# It-s_Time_Do.net
KiCad netlist of a schematic drawn in EAGLE
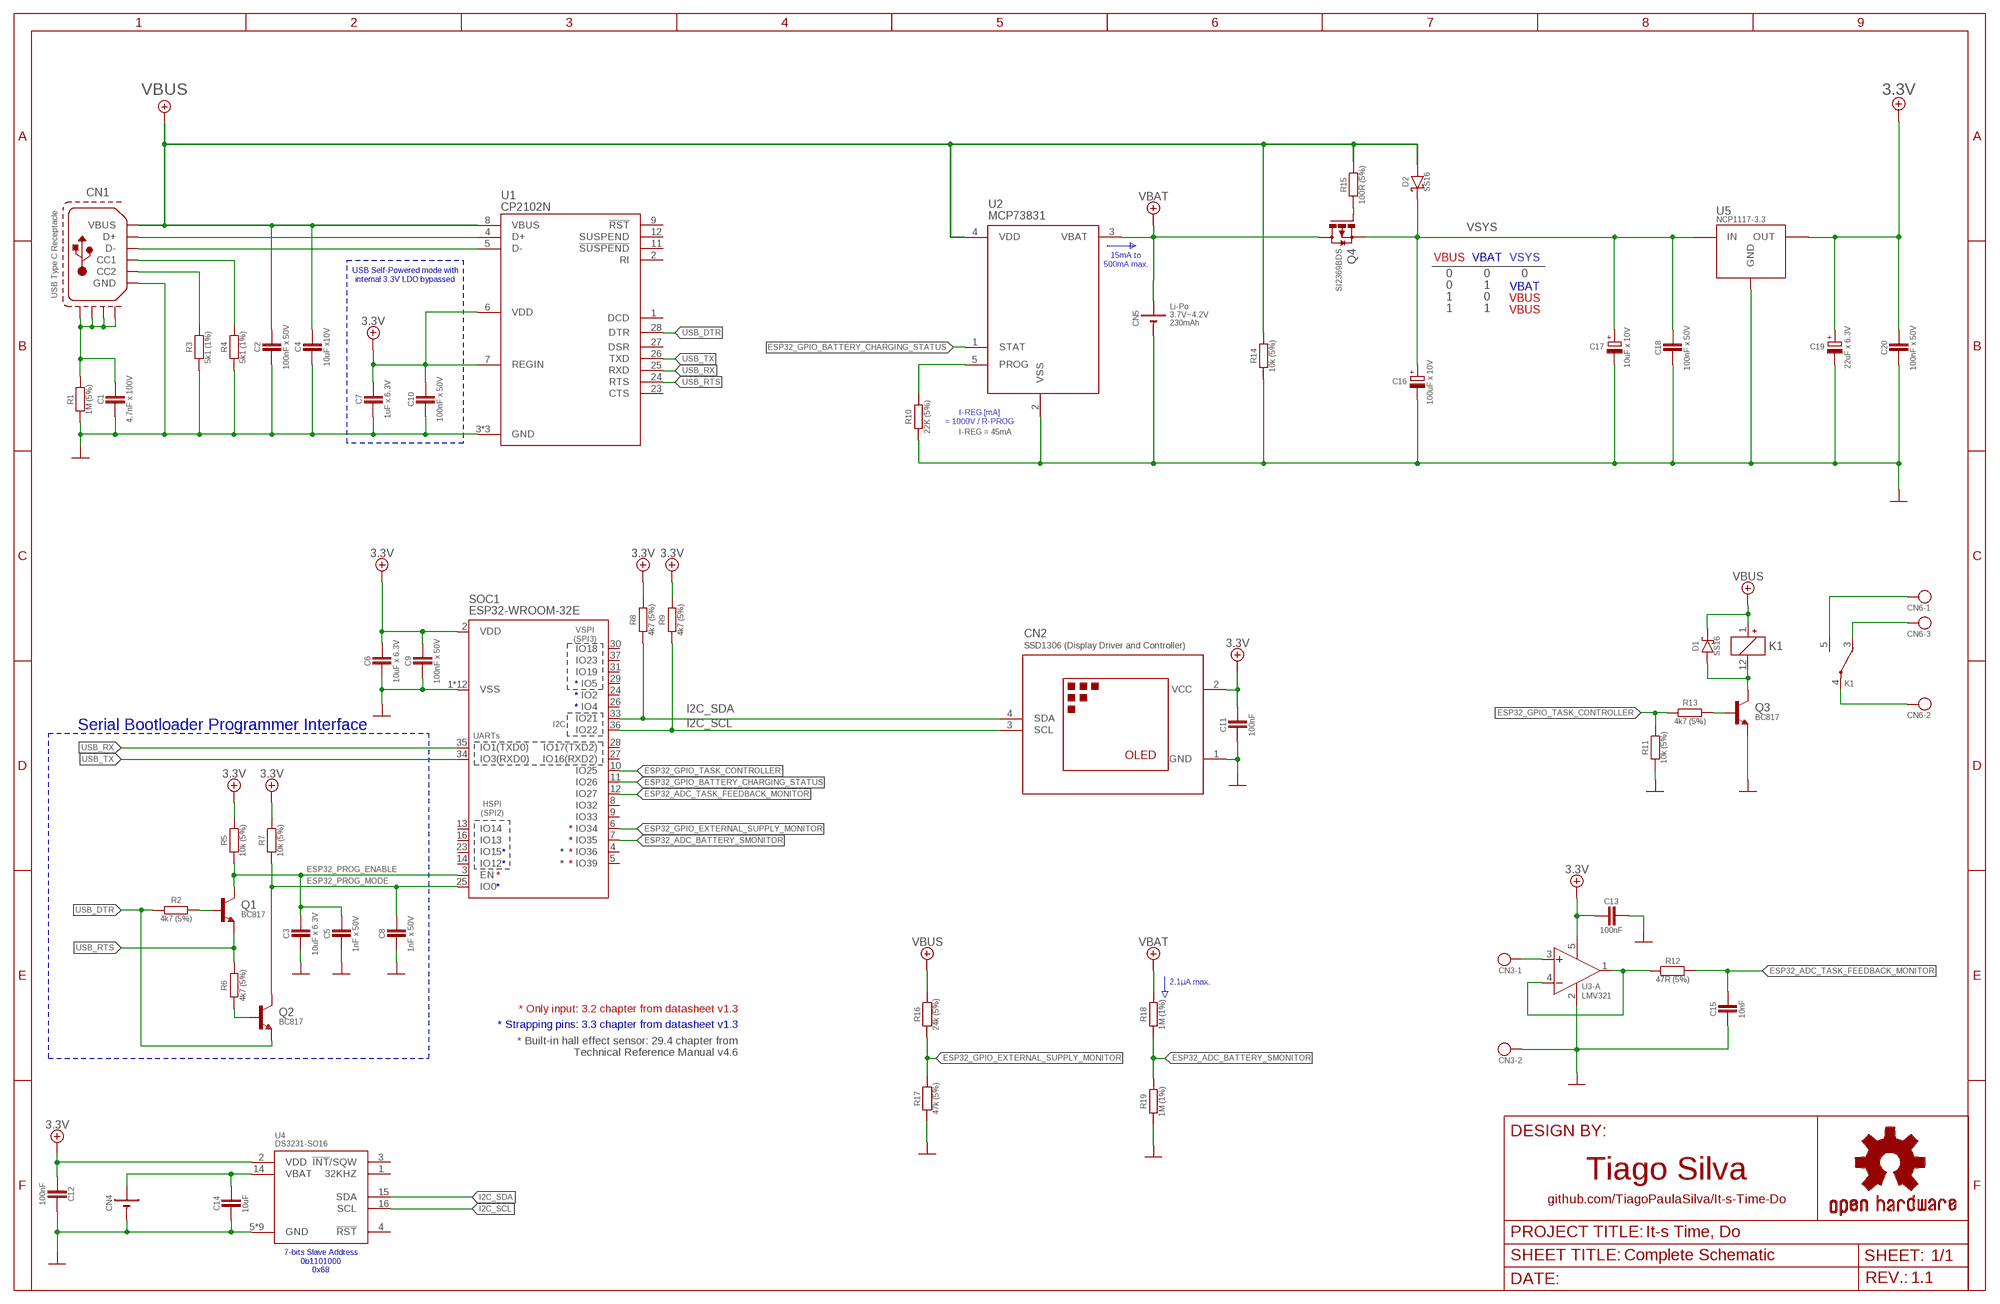
[diagram p0: schematic, sheet 1]

(export (version "E")
  (design (tool "Eeschema 10.0.6"))
  (components
    (comp (ref "C1")
      (value "4.7nF x 100V")
      (footprint "eagle-import:C0603")
      (libsource (lib "eagle-import") (part "C_0603"))
    )
    (comp (ref "C2")
      (value "100nF x 50V")
      (footprint "eagle-import:C0603")
      (libsource (lib "eagle-import") (part "C_0603"))
    )
    (comp (ref "C3")
      (value "10uF x 6.3V")
      (footprint "eagle-import:C0603")
      (libsource (lib "eagle-import") (part "C_0603"))
    )
    (comp (ref "C4")
      (value "10uF x10V")
      (footprint "eagle-import:C0603")
      (libsource (lib "eagle-import") (part "C_0603"))
    )
    (comp (ref "C5")
      (value "1nF x 50V")
      (footprint "eagle-import:C0603")
      (libsource (lib "eagle-import") (part "C_0603"))
    )
    (comp (ref "C6")
      (value "10uF x 6.3V")
      (footprint "eagle-import:C0603")
      (libsource (lib "eagle-import") (part "C_0603"))
    )
    (comp (ref "C7")
      (value "1uF x 6.3V")
      (footprint "eagle-import:C0603")
      (libsource (lib "eagle-import") (part "C_0603"))
    )
    (comp (ref "C8")
      (value "1nF x 50V")
      (footprint "eagle-import:C0603")
      (libsource (lib "eagle-import") (part "C_0603"))
    )
    (comp (ref "C9")
      (value "100nF x 50V")
      (footprint "eagle-import:C0603")
      (libsource (lib "eagle-import") (part "C_0603"))
    )
    (comp (ref "C10")
      (value "100nF x 50V")
      (footprint "eagle-import:C0603")
      (libsource (lib "eagle-import") (part "C_0603"))
    )
    (comp (ref "C11")
      (value "100nF")
      (footprint "eagle-import:C0603")
      (libsource (lib "eagle-import") (part "C_0603"))
    )
    (comp (ref "C12")
      (value "100nF")
      (footprint "eagle-import:C0603")
      (libsource (lib "eagle-import") (part "C_0603"))
    )
    (comp (ref "C13")
      (value "100nF")
      (footprint "eagle-import:C0603")
      (libsource (lib "eagle-import") (part "C_0603"))
    )
    (comp (ref "C14")
      (value "10uF")
      (footprint "eagle-import:C0603")
      (fields (field (name "PARTNO") "GRJ155R60J106ME11D"))
      (libsource (lib "eagle-import") (part "C_0603"))
    )
    (comp (ref "C15")
      (value "10nF")
      (footprint "eagle-import:C0603")
      (libsource (lib "eagle-import") (part "C_0603"))
    )
    (comp (ref "C16")
      (value "100uF x 10V")
      (footprint "eagle-import:PTH-5MM")
      (libsource (lib "eagle-import") (part "CP_5MM"))
    )
    (comp (ref "C17")
      (value "10uF x 10V")
      (footprint "eagle-import:C1206_POL")
      (description "Tantalum Electrolytic Capacitors (Low ESR)")
      (libsource (lib "eagle-import") (part "CP_1206_POL"))
    )
    (comp (ref "C18")
      (value "100nF x 50V")
      (footprint "eagle-import:C0603")
      (libsource (lib "eagle-import") (part "C_0603"))
    )
    (comp (ref "C19")
      (value "22uF x 6.3V")
      (footprint "eagle-import:C1206_POL")
      (description "Tantalum Electrolytic Capacitors (Low ESR)")
      (libsource (lib "eagle-import") (part "CP_1206_POL"))
    )
    (comp (ref "C20")
      (value "100nF x 50V")
      (footprint "eagle-import:C0603")
      (libsource (lib "eagle-import") (part "C_0603"))
    )
    (comp (ref "CN1")
      (value "USB Type C Receptacle")
      (footprint "eagle-import:USB-C-16P-2LAYER-PADS")
      (libsource (lib "eagle-import") (part "USB-C-16P-2LAYERS"))
    )
    (comp (ref "CN2")
      (value "OLED-MODULE-I2C-SOCKET")
      (footprint "eagle-import:PIN_HEADER_1X4_FEMALE")
      (fields (field (name "FAMILY") "SSD1306 (Display Driver and Controller)"))
      (libsource (lib "eagle-import") (part "OLED-MODULE-I2C-SOCKET"))
    )
    (comp (ref "CN3")
      (value "2P-MINI-FIT-JR")
      (footprint "eagle-import:MINI-FIT-JR-2P")
      (libsource (lib "eagle-import") (part "2P-MINI-FIT-JR"))
    )
    (comp (ref "CN4")
      (value "CR1220")
      (footprint "eagle-import:CR1220_1225_HOLDER2")
      (libsource (lib "eagle-import") (part "CELL-HARWIN"))
    )
    (comp (ref "CN5")
      (value "BATTERY")
      (footprint "eagle-import:JST-PH-2P-H")
      (fields
        (field (name "CAPACITY") "230mAh")
        (field (name "TYPE") "Li-Po")
        (field (name "VOLTAGE") "3.7V~4.2V")
      )
      (libsource (lib "eagle-import") (part "CELL-JST-PH-2P-H"))
    )
    (comp (ref "CN6")
      (value "3P-MINI-FIT-JR")
      (footprint "eagle-import:MINI-FIT-JR-3P")
      (libsource (lib "eagle-import") (part "3P-MINI-FIT-JR"))
    )
    (comp (ref "D1")
      (value "FM4004")
      (footprint "eagle-import:DO-214AC")
      (fields (field (name "FAMILY") "SS16") (field (name "PN") "FM4004W-W"))
      (libsource (lib "eagle-import") (part "SCHOTTKY-SS16"))
    )
    (comp (ref "D2")
      (value "SCHOTTKY-SS16")
      (footprint "eagle-import:DO-214AC")
      (fields (field (name "FAMILY") "SS16"))
      (libsource (lib "eagle-import") (part "SCHOTTKY-SS16"))
    )
    (comp (ref "K1")
      (value "DPDT-SMD")
      (footprint "eagle-import:EE2-5NU")
      (libsource (lib "eagle-import") (part "DPDT-SMD"))
    )
    (comp (ref "Q1")
      (value "NPN-BC817")
      (footprint "eagle-import:SOT23-3")
      (fields (field (name "FAMILY") "BC817"))
      (libsource (lib "eagle-import") (part "NPN-BC817"))
    )
    (comp (ref "Q2")
      (value "NPN-BC817")
      (footprint "eagle-import:SOT23-3")
      (fields (field (name "FAMILY") "BC817"))
      (libsource (lib "eagle-import") (part "NPN-BC817"))
    )
    (comp (ref "Q3")
      (value "BC817")
      (footprint "eagle-import:SOT23-3")
      (fields (field (name "FAMILY") "BC817") (field (name "PN") "BC817K-16HR"))
      (libsource (lib "eagle-import") (part "NPN-BC817"))
    )
    (comp (ref "Q4")
      (value "P-FET-ENHANCEMENT-SI2369BDS")
      (footprint "eagle-import:SOT23-3")
      (fields (field (name "FAMILY") "SI2369BDS"))
      (libsource (lib "eagle-import") (part "P-FET-ENHANCEMENT-SI2369BDS"))
    )
    (comp (ref "R1")
      (value "1M (5%)")
      (footprint "eagle-import:R0603")
      (libsource (lib "eagle-import") (part "R_0603"))
    )
    (comp (ref "R2")
      (value "4k7 (5%)")
      (footprint "eagle-import:R0603")
      (libsource (lib "eagle-import") (part "R_0603"))
    )
    (comp (ref "R3")
      (value "5k1 (1%)")
      (footprint "eagle-import:R0603")
      (libsource (lib "eagle-import") (part "R_0603"))
    )
    (comp (ref "R4")
      (value "5k1 (1%)")
      (footprint "eagle-import:R0603")
      (libsource (lib "eagle-import") (part "R_0603"))
    )
    (comp (ref "R5")
      (value "10k (5%)")
      (footprint "eagle-import:R0603")
      (libsource (lib "eagle-import") (part "R_0603"))
    )
    (comp (ref "R6")
      (value "4k7 (5%)")
      (footprint "eagle-import:R0603")
      (libsource (lib "eagle-import") (part "R_0603"))
    )
    (comp (ref "R7")
      (value "10k (5%)")
      (footprint "eagle-import:R0603")
      (libsource (lib "eagle-import") (part "R_0603"))
    )
    (comp (ref "R8")
      (value "4k7 (5%)")
      (footprint "eagle-import:R0603")
      (libsource (lib "eagle-import") (part "R_0603"))
    )
    (comp (ref "R9")
      (value "4k7 (5%)")
      (footprint "eagle-import:R0603")
      (libsource (lib "eagle-import") (part "R_0603"))
    )
    (comp (ref "R10")
      (value "22K (5%)")
      (footprint "eagle-import:R0603")
      (libsource (lib "eagle-import") (part "R_0603"))
    )
    (comp (ref "R11")
      (value "10k (5%)")
      (footprint "eagle-import:R0603")
      (libsource (lib "eagle-import") (part "R_0603"))
    )
    (comp (ref "R12")
      (value "47R (5%)")
      (footprint "eagle-import:R0603")
      (libsource (lib "eagle-import") (part "R_0603"))
    )
    (comp (ref "R13")
      (value "4k7 (5%)")
      (footprint "eagle-import:R0603")
      (libsource (lib "eagle-import") (part "R_0603"))
    )
    (comp (ref "R14")
      (value "10k (5%)")
      (footprint "eagle-import:R0603")
      (libsource (lib "eagle-import") (part "R_0603"))
    )
    (comp (ref "R15")
      (value "100R (5%)")
      (footprint "eagle-import:R0603")
      (libsource (lib "eagle-import") (part "R_0603"))
    )
    (comp (ref "R16")
      (value "24k (5%)")
      (footprint "eagle-import:R0603")
      (fields (field (name "PARTNO") "RC0402FR-0724KL"))
      (libsource (lib "eagle-import") (part "R_0603"))
    )
    (comp (ref "R17")
      (value "47k (5%)")
      (footprint "eagle-import:R0603")
      (fields (field (name "PARTNO") "RC0402FR-0747KL"))
      (libsource (lib "eagle-import") (part "R_0603"))
    )
    (comp (ref "R18")
      (value "1M (1%)")
      (footprint "eagle-import:R0603")
      (libsource (lib "eagle-import") (part "R_0603"))
    )
    (comp (ref "R19")
      (value "1M (1%)")
      (footprint "eagle-import:R0603")
      (libsource (lib "eagle-import") (part "R_0603"))
    )
    (comp (ref "SOC1")
      (value "ESP32-WROOM-32E")
      (footprint "eagle-import:ESP32-WROOM-32E")
      (libsource (lib "eagle-import") (part "ESP32-WROOM-32E-N4"))
    )
    (comp (ref "U1")
      (value "CP2102N")
      (footprint "eagle-import:QFN-28")
      (libsource (lib "eagle-import") (part "CP2102N"))
    )
    (comp (ref "U2")
      (value "MCP73831")
      (footprint "eagle-import:SOT-23-5")
      (libsource (lib "eagle-import") (part "MCP73831T-2ACI/OT"))
    )
    (comp (ref "U3")
      (value "LMV321")
      (footprint "eagle-import:SOT-23-5")
      (libsource (lib "eagle-import") (part "SINGLE-LMV321"))
    )
    (comp (ref "U4")
      (value "DS3231-SO16")
      (footprint "eagle-import:SOIC-16W_(SO16)")
      (libsource (lib "eagle-import") (part "DS3231-SO16"))
    )
    (comp (ref "U5")
      (value "1117-3.3V")
      (footprint "eagle-import:SOT-223-3")
      (fields (field (name "FAMILY") "LT1117-3.3") (field (name "FAMILY_1") "NCP1117-3.3"))
      (libsource (lib "eagle-import") (part "1117-3.3V"))
    )
  )
  (nets
    (net (code "1") (name "/ESP32_PROG_ENABLE") (class "Default")
      (node (ref "C3") (pin "1") (pinfunction "1_1") (pintype "passive"))
      (node (ref "C5") (pin "1") (pinfunction "1_1") (pintype "passive"))
      (node (ref "Q1") (pin "3") (pinfunction "C_3") (pintype "passive"))
      (node (ref "R5") (pin "2") (pinfunction "2_2") (pintype "passive"))
      (node (ref "SOC1") (pin "3") (pinfunction "EN_3") (pintype "input"))
    )
    (net (code "2") (name "/ESP32_PROG_MODE") (class "Default")
      (node (ref "C8") (pin "1") (pinfunction "1_1") (pintype "passive"))
      (node (ref "Q2") (pin "3") (pinfunction "C_3") (pintype "passive"))
      (node (ref "R7") (pin "2") (pinfunction "2_2") (pintype "passive"))
      (node (ref "SOC1") (pin "25") (pinfunction "IO0_25") (pintype "bidirectional"))
    )
    (net (code "3") (name "/VSYS") (class "Default")
      (node (ref "C16") (pin "1") (pinfunction "+_1") (pintype "passive"))
      (node (ref "C17") (pin "1") (pinfunction "+_1") (pintype "passive"))
      (node (ref "C18") (pin "1") (pinfunction "1_1") (pintype "passive"))
      (node (ref "D2") (pin "1") (pinfunction "K_1") (pintype "passive"))
      (node (ref "Q4") (pin "2") (pinfunction "S_2") (pintype "passive"))
      (node (ref "U5") (pin "3") (pinfunction "IN_3") (pintype "bidirectional"))
    )
    (net (code "4") (name "0V") (class "Default")
      (node (ref "C1") (pin "1") (pinfunction "1_1") (pintype "passive"))
      (node (ref "C10") (pin "1") (pinfunction "1_1") (pintype "passive"))
      (node (ref "C11") (pin "2") (pinfunction "2_2") (pintype "passive"))
      (node (ref "C12") (pin "1") (pinfunction "1_1") (pintype "passive"))
      (node (ref "C13") (pin "1") (pinfunction "1_1") (pintype "passive"))
      (node (ref "C14") (pin "2") (pinfunction "2_2") (pintype "passive"))
      (node (ref "C15") (pin "2") (pinfunction "2_2") (pintype "passive"))
      (node (ref "C16") (pin "2") (pinfunction "-_2") (pintype "passive"))
      (node (ref "C17") (pin "2") (pinfunction "-_2") (pintype "passive"))
      (node (ref "C18") (pin "2") (pinfunction "2_2") (pintype "passive"))
      (node (ref "C19") (pin "2") (pinfunction "-_2") (pintype "passive"))
      (node (ref "C2") (pin "1") (pinfunction "1_1") (pintype "passive"))
      (node (ref "C20") (pin "2") (pinfunction "2_2") (pintype "passive"))
      (node (ref "C3") (pin "2") (pinfunction "2_2") (pintype "passive"))
      (node (ref "C4") (pin "1") (pinfunction "1_1") (pintype "passive"))
      (node (ref "C5") (pin "2") (pinfunction "2_2") (pintype "passive"))
      (node (ref "C6") (pin "2") (pinfunction "2_2") (pintype "passive"))
      (node (ref "C7") (pin "1") (pinfunction "1_1") (pintype "passive"))
      (node (ref "C8") (pin "2") (pinfunction "2_2") (pintype "passive"))
      (node (ref "C9") (pin "2") (pinfunction "2_2") (pintype "passive"))
      (node (ref "CN1") (pin "GND") (pinfunction "GND_GND") (pintype "bidirectional"))
      (node (ref "CN1") (pin "GND2") (pinfunction "GND_GND2") (pintype "bidirectional"))
      (node (ref "CN2") (pin "1") (pinfunction "GND_1") (pintype "power_in"))
      (node (ref "CN3") (pin "2") (pinfunction "P$1_2") (pintype "passive"))
      (node (ref "CN4") (pin "2") (pinfunction "-_2") (pintype "passive"))
      (node (ref "CN5") (pin "2") (pinfunction "-_2") (pintype "passive"))
      (node (ref "Q3") (pin "2") (pinfunction "E_2") (pintype "passive"))
      (node (ref "R1") (pin "2") (pinfunction "2_2") (pintype "passive"))
      (node (ref "R10") (pin "1") (pinfunction "1_1") (pintype "passive"))
      (node (ref "R11") (pin "2") (pinfunction "2_2") (pintype "passive"))
      (node (ref "R14") (pin "1") (pinfunction "1_1") (pintype "passive"))
      (node (ref "R17") (pin "2") (pinfunction "2_2") (pintype "passive"))
      (node (ref "R19") (pin "1") (pinfunction "1_1") (pintype "passive"))
      (node (ref "R3") (pin "2") (pinfunction "2_2") (pintype "passive"))
      (node (ref "R4") (pin "2") (pinfunction "2_2") (pintype "passive"))
      (node (ref "SOC1") (pin "1") (pinfunction "VSS_1") (pintype "power_in"))
      (node (ref "SOC1") (pin "15") (pinfunction "VSS_15") (pintype "power_in"))
      (node (ref "SOC1") (pin "38") (pinfunction "VSS_38") (pintype "power_in"))
      (node (ref "SOC1") (pin "E1") (pinfunction "VSS_E1") (pintype "power_in"))
      (node (ref "SOC1") (pin "E2") (pinfunction "VSS_E2") (pintype "power_in"))
      (node (ref "SOC1") (pin "E3") (pinfunction "VSS_E3") (pintype "power_in"))
      (node (ref "SOC1") (pin "E4") (pinfunction "VSS_E4") (pintype "power_in"))
      (node (ref "SOC1") (pin "E5") (pinfunction "VSS_E5") (pintype "power_in"))
      (node (ref "SOC1") (pin "E6") (pinfunction "VSS_E6") (pintype "power_in"))
      (node (ref "SOC1") (pin "E7") (pinfunction "VSS_E7") (pintype "power_in"))
      (node (ref "SOC1") (pin "E8") (pinfunction "VSS_E8") (pintype "power_in"))
      (node (ref "SOC1") (pin "E9") (pinfunction "VSS_E9") (pintype "power_in"))
      (node (ref "U1") (pin "3") (pinfunction "GND_3") (pintype "power_in"))
      (node (ref "U1") (pin "EXP") (pinfunction "GND_EXP") (pintype "power_in"))
      (node (ref "U1") (pin "M") (pinfunction "GND_M") (pintype "power_in"))
      (node (ref "U2") (pin "2") (pinfunction "VSS_2") (pintype "power_in"))
      (node (ref "U3") (pin "2") (pinfunction "V-_2") (pintype "power_in"))
      (node (ref "U4") (pin "10") (pinfunction "GND_10") (pintype "power_in"))
      (node (ref "U4") (pin "11") (pinfunction "GND_11") (pintype "power_in"))
      (node (ref "U4") (pin "12") (pinfunction "GND_12") (pintype "power_in"))
      (node (ref "U4") (pin "13") (pinfunction "GND_13") (pintype "power_in"))
      (node (ref "U4") (pin "5") (pinfunction "GND_5") (pintype "power_in"))
      (node (ref "U4") (pin "6") (pinfunction "GND_6") (pintype "power_in"))
      (node (ref "U4") (pin "7") (pinfunction "GND_7") (pintype "power_in"))
      (node (ref "U4") (pin "8") (pinfunction "GND_8") (pintype "power_in"))
      (node (ref "U4") (pin "9") (pinfunction "GND_9") (pintype "power_in"))
      (node (ref "U5") (pin "1") (pinfunction "GND_1") (pintype "bidirectional"))
    )
    (net (code "5") (name "3.3V") (class "Default")
      (node (ref "C10") (pin "2") (pinfunction "2_2") (pintype "passive"))
      (node (ref "C11") (pin "1") (pinfunction "1_1") (pintype "passive"))
      (node (ref "C12") (pin "2") (pinfunction "2_2") (pintype "passive"))
      (node (ref "C13") (pin "2") (pinfunction "2_2") (pintype "passive"))
      (node (ref "C19") (pin "1") (pinfunction "+_1") (pintype "passive"))
      (node (ref "C20") (pin "1") (pinfunction "1_1") (pintype "passive"))
      (node (ref "C6") (pin "1") (pinfunction "1_1") (pintype "passive"))
      (node (ref "C7") (pin "2") (pinfunction "2_2") (pintype "passive"))
      (node (ref "C9") (pin "1") (pinfunction "1_1") (pintype "passive"))
      (node (ref "CN2") (pin "2") (pinfunction "VCC_2") (pintype "power_in"))
      (node (ref "R5") (pin "1") (pinfunction "1_1") (pintype "passive"))
      (node (ref "R7") (pin "1") (pinfunction "1_1") (pintype "passive"))
      (node (ref "R8") (pin "2") (pinfunction "2_2") (pintype "passive"))
      (node (ref "R9") (pin "2") (pinfunction "2_2") (pintype "passive"))
      (node (ref "SOC1") (pin "2") (pinfunction "VDD_2") (pintype "power_in"))
      (node (ref "U1") (pin "6") (pinfunction "VDD_6") (pintype "power_in"))
      (node (ref "U1") (pin "7") (pinfunction "REGIN_7") (pintype "passive"))
      (node (ref "U3") (pin "5") (pinfunction "V+_5") (pintype "power_in"))
      (node (ref "U4") (pin "2") (pinfunction "VDD_2") (pintype "power_in"))
      (node (ref "U5") (pin "2") (pinfunction "OUT_2") (pintype "bidirectional"))
      (node (ref "U5") (pin "4") (pinfunction "OUT_4") (pintype "bidirectional"))
    )
    (net (code "6") (name "ESP32_ADC_BATTERY_SMONITOR") (class "Default")
      (node (ref "R18") (pin "1") (pinfunction "1_1") (pintype "passive"))
      (node (ref "R19") (pin "2") (pinfunction "2_2") (pintype "passive"))
      (node (ref "SOC1") (pin "7") (pinfunction "IO35_7") (pintype "bidirectional"))
    )
    (net (code "7") (name "ESP32_ADC_TASK_FEEDBACK_MONITOR") (class "Default")
      (node (ref "C15") (pin "1") (pinfunction "1_1") (pintype "passive"))
      (node (ref "R12") (pin "2") (pinfunction "2_2") (pintype "passive"))
      (node (ref "SOC1") (pin "12") (pinfunction "IO27_12") (pintype "bidirectional"))
    )
    (net (code "8") (name "ESP32_GPIO_BATTERY_CHARGING_STATUS") (class "Default")
      (node (ref "SOC1") (pin "11") (pinfunction "IO26_11") (pintype "bidirectional"))
      (node (ref "U2") (pin "1") (pinfunction "STAT_1") (pintype "output"))
    )
    (net (code "9") (name "ESP32_GPIO_EXTERNAL_SUPPLY_MONITOR") (class "Default")
      (node (ref "R16") (pin "2") (pinfunction "2_2") (pintype "passive"))
      (node (ref "R17") (pin "1") (pinfunction "1_1") (pintype "passive"))
      (node (ref "SOC1") (pin "6") (pinfunction "IO34_6") (pintype "bidirectional"))
    )
    (net (code "10") (name "ESP32_GPIO_TASK_CONTROLLER") (class "Default")
      (node (ref "R11") (pin "1") (pinfunction "1_1") (pintype "passive"))
      (node (ref "R13") (pin "2") (pinfunction "2_2") (pintype "passive"))
      (node (ref "SOC1") (pin "10") (pinfunction "IO25_10") (pintype "bidirectional"))
    )
    (net (code "11") (name "I2C_SCL") (class "Default")
      (node (ref "CN2") (pin "3") (pinfunction "SCL_3") (pintype "bidirectional"))
      (node (ref "R9") (pin "1") (pinfunction "1_1") (pintype "passive"))
      (node (ref "SOC1") (pin "36") (pinfunction "IO22_36") (pintype "bidirectional"))
      (node (ref "U4") (pin "16") (pinfunction "SCL_16") (pintype "bidirectional"))
    )
    (net (code "12") (name "I2C_SDA") (class "Default")
      (node (ref "CN2") (pin "4") (pinfunction "SDA_4") (pintype "bidirectional"))
      (node (ref "R8") (pin "1") (pinfunction "1_1") (pintype "passive"))
      (node (ref "SOC1") (pin "33") (pinfunction "IO21_33") (pintype "bidirectional"))
      (node (ref "U4") (pin "15") (pinfunction "SDA_15") (pintype "bidirectional"))
    )
    (net (code "13") (name "Net-(CN1-CC1)") (class "Default")
      (node (ref "CN1") (pin "A5") (pinfunction "CC1_A5") (pintype "bidirectional"))
      (node (ref "R4") (pin "1") (pinfunction "1_1") (pintype "passive"))
    )
    (net (code "14") (name "Net-(CN1-CC2)") (class "Default")
      (node (ref "CN1") (pin "B5") (pinfunction "CC2_B5") (pintype "bidirectional"))
      (node (ref "R3") (pin "1") (pinfunction "1_1") (pintype "passive"))
    )
    (net (code "15") (name "Net-(CN1-S1)") (class "Default")
      (node (ref "C1") (pin "2") (pinfunction "2_2") (pintype "passive"))
      (node (ref "CN1") (pin "SHLD1") (pinfunction "S1_SHLD1") (pintype "passive"))
      (node (ref "CN1") (pin "SHLD2") (pinfunction "S2_SHLD2") (pintype "passive"))
      (node (ref "CN1") (pin "SHLD3") (pinfunction "S3_SHLD3") (pintype "passive"))
      (node (ref "CN1") (pin "SHLD4") (pinfunction "S4_SHLD4") (pintype "passive"))
      (node (ref "R1") (pin "1") (pinfunction "1_1") (pintype "passive"))
    )
    (net (code "16") (name "Net-(CN3A-P$1)") (class "Default")
      (node (ref "CN3") (pin "1") (pinfunction "P$1_1") (pintype "passive"))
      (node (ref "U3") (pin "3") (pinfunction "+IN_3") (pintype "input"))
    )
    (net (code "17") (name "Net-(CN4-+)") (class "Default")
      (node (ref "C14") (pin "1") (pinfunction "1_1") (pintype "passive"))
      (node (ref "CN4") (pin "1") (pinfunction "+_1") (pintype "passive"))
      (node (ref "U4") (pin "14") (pinfunction "VBAT_14") (pintype "power_in"))
    )
    (net (code "18") (name "Net-(CN6A-P$1)") (class "Default")
      (node (ref "CN6") (pin "1") (pinfunction "P$1_1") (pintype "passive"))
      (node (ref "K1") (pin "5") (pinfunction "NO_5") (pintype "passive"))
    )
    (net (code "19") (name "Net-(CN6B-P$1)") (class "Default")
      (node (ref "CN6") (pin "2") (pinfunction "P$1_2") (pintype "passive"))
      (node (ref "K1") (pin "4") (pinfunction "COM_4") (pintype "passive"))
    )
    (net (code "20") (name "Net-(CN6C-P$1)") (class "Default")
      (node (ref "CN6") (pin "3") (pinfunction "P$1_3") (pintype "passive"))
      (node (ref "K1") (pin "3") (pinfunction "NC_3") (pintype "passive"))
    )
    (net (code "21") (name "Net-(D1-A)") (class "Default")
      (node (ref "D1") (pin "2") (pinfunction "A_2") (pintype "passive"))
      (node (ref "K1") (pin "12") (pinfunction "-_12") (pintype "passive"))
      (node (ref "Q3") (pin "3") (pinfunction "C_3") (pintype "passive"))
    )
    (net (code "22") (name "Net-(Q1-B)") (class "Default")
      (node (ref "Q1") (pin "1") (pinfunction "B_1") (pintype "passive"))
      (node (ref "R2") (pin "1") (pinfunction "1_1") (pintype "passive"))
    )
    (net (code "23") (name "Net-(Q2-B)") (class "Default")
      (node (ref "Q2") (pin "1") (pinfunction "B_1") (pintype "passive"))
      (node (ref "R6") (pin "1") (pinfunction "1_1") (pintype "passive"))
    )
    (net (code "24") (name "Net-(Q3-B)") (class "Default")
      (node (ref "Q3") (pin "1") (pinfunction "B_1") (pintype "passive"))
      (node (ref "R13") (pin "1") (pinfunction "1_1") (pintype "passive"))
    )
    (net (code "25") (name "Net-(Q4-G)") (class "Default")
      (node (ref "Q4") (pin "1") (pinfunction "G_1") (pintype "passive"))
      (node (ref "R15") (pin "2") (pinfunction "2_2") (pintype "passive"))
    )
    (net (code "26") (name "Net-(U1-D+)") (class "Default")
      (node (ref "CN1") (pin "A6") (pinfunction "D+_A6") (pintype "bidirectional"))
      (node (ref "CN1") (pin "B6") (pinfunction "D+_B6") (pintype "bidirectional"))
      (node (ref "U1") (pin "4") (pinfunction "D+_4") (pintype "bidirectional"))
    )
    (net (code "27") (name "Net-(U1-D-)") (class "Default")
      (node (ref "CN1") (pin "A7") (pinfunction "D-_A7") (pintype "bidirectional"))
      (node (ref "CN1") (pin "B7") (pinfunction "D-_B7") (pintype "bidirectional"))
      (node (ref "U1") (pin "5") (pinfunction "D-_5") (pintype "bidirectional"))
    )
    (net (code "28") (name "Net-(U2-PROG)") (class "Default")
      (node (ref "R10") (pin "2") (pinfunction "2_2") (pintype "passive"))
      (node (ref "U2") (pin "5") (pinfunction "PROG_5") (pintype "input"))
    )
    (net (code "29") (name "Net-(U3A--IN)") (class "Default")
      (node (ref "R12") (pin "1") (pinfunction "1_1") (pintype "passive"))
      (node (ref "U3") (pin "1") (pinfunction "OUT_1") (pintype "output"))
      (node (ref "U3") (pin "4") (pinfunction "-IN_4") (pintype "input"))
    )
    (net (code "30") (name "USB_DTR") (class "Default")
      (node (ref "Q2") (pin "2") (pinfunction "E_2") (pintype "passive"))
      (node (ref "R2") (pin "2") (pinfunction "2_2") (pintype "passive"))
      (node (ref "U1") (pin "28") (pinfunction "DTR_28") (pintype "output"))
    )
    (net (code "31") (name "USB_RTS") (class "Default")
      (node (ref "Q1") (pin "2") (pinfunction "E_2") (pintype "passive"))
      (node (ref "R6") (pin "2") (pinfunction "2_2") (pintype "passive"))
      (node (ref "U1") (pin "24") (pinfunction "RTS_24") (pintype "output"))
    )
    (net (code "32") (name "USB_RX") (class "Default")
      (node (ref "SOC1") (pin "35") (pinfunction "IO1(TXD0)_35") (pintype "bidirectional"))
      (node (ref "U1") (pin "25") (pinfunction "RXD_25") (pintype "input"))
    )
    (net (code "33") (name "USB_TX") (class "Default")
      (node (ref "SOC1") (pin "34") (pinfunction "IO3(RXD0)_34") (pintype "bidirectional"))
      (node (ref "U1") (pin "26") (pinfunction "TXD_26") (pintype "output"))
    )
    (net (code "34") (name "VBAT") (class "Default")
      (node (ref "CN5") (pin "1") (pinfunction "+_1") (pintype "passive"))
      (node (ref "Q4") (pin "3") (pinfunction "D_3") (pintype "passive"))
      (node (ref "R18") (pin "2") (pinfunction "2_2") (pintype "passive"))
      (node (ref "U2") (pin "3") (pinfunction "VBAT_3") (pintype "bidirectional"))
    )
    (net (code "35") (name "VBUS") (class "Default")
      (node (ref "C2") (pin "2") (pinfunction "2_2") (pintype "passive"))
      (node (ref "C4") (pin "2") (pinfunction "2_2") (pintype "passive"))
      (node (ref "CN1") (pin "VBUS1") (pinfunction "VBUS_VBUS1") (pintype "bidirectional"))
      (node (ref "CN1") (pin "VBUS2") (pinfunction "VBUS_VBUS2") (pintype "bidirectional"))
      (node (ref "D1") (pin "1") (pinfunction "K_1") (pintype "passive"))
      (node (ref "D2") (pin "2") (pinfunction "A_2") (pintype "passive"))
      (node (ref "K1") (pin "1") (pinfunction "+_1") (pintype "passive"))
      (node (ref "R14") (pin "2") (pinfunction "2_2") (pintype "passive"))
      (node (ref "R15") (pin "1") (pinfunction "1_1") (pintype "passive"))
      (node (ref "R16") (pin "1") (pinfunction "1_1") (pintype "passive"))
      (node (ref "U1") (pin "8") (pinfunction "VBUS_8") (pintype "passive"))
      (node (ref "U2") (pin "4") (pinfunction "VDD_4") (pintype "power_in"))
    )
    (net (code "36") (name "unconnected-(SOC1-IO2-Pad24)") (class "Default")
      (node (ref "SOC1") (pin "24") (pinfunction "IO2_24") (pintype "bidirectional"))
    )
    (net (code "37") (name "unconnected-(SOC1-IO4-Pad26)") (class "Default")
      (node (ref "SOC1") (pin "26") (pinfunction "IO4_26") (pintype "bidirectional"))
    )
    (net (code "38") (name "unconnected-(SOC1-IO5-Pad29)") (class "Default")
      (node (ref "SOC1") (pin "29") (pinfunction "IO5_29") (pintype "bidirectional"))
    )
    (net (code "39") (name "unconnected-(SOC1-IO12-Pad14)") (class "Default")
      (node (ref "SOC1") (pin "14") (pinfunction "IO12_14") (pintype "bidirectional"))
    )
    (net (code "40") (name "unconnected-(SOC1-IO13-Pad16)") (class "Default")
      (node (ref "SOC1") (pin "16") (pinfunction "IO13_16") (pintype "bidirectional"))
    )
    (net (code "41") (name "unconnected-(SOC1-IO14-Pad13)") (class "Default")
      (node (ref "SOC1") (pin "13") (pinfunction "IO14_13") (pintype "bidirectional"))
    )
    (net (code "42") (name "unconnected-(SOC1-IO15-Pad23)") (class "Default")
      (node (ref "SOC1") (pin "23") (pinfunction "IO15_23") (pintype "bidirectional"))
    )
    (net (code "43") (name "unconnected-(SOC1-IO16(RXD2)-Pad27)") (class "Default")
      (node (ref "SOC1") (pin "27") (pinfunction "IO16(RXD2)_27") (pintype "bidirectional"))
    )
    (net (code "44") (name "unconnected-(SOC1-IO17(TXD2)-Pad28)") (class "Default")
      (node (ref "SOC1") (pin "28") (pinfunction "IO17(TXD2)_28") (pintype "bidirectional"))
    )
    (net (code "45") (name "unconnected-(SOC1-IO18-Pad30)") (class "Default")
      (node (ref "SOC1") (pin "30") (pinfunction "IO18_30") (pintype "bidirectional"))
    )
    (net (code "46") (name "unconnected-(SOC1-IO19-Pad31)") (class "Default")
      (node (ref "SOC1") (pin "31") (pinfunction "IO19_31") (pintype "bidirectional"))
    )
    (net (code "47") (name "unconnected-(SOC1-IO23-Pad37)") (class "Default")
      (node (ref "SOC1") (pin "37") (pinfunction "IO23_37") (pintype "bidirectional"))
    )
    (net (code "48") (name "unconnected-(SOC1-IO32-Pad8)") (class "Default")
      (node (ref "SOC1") (pin "8") (pinfunction "IO32_8") (pintype "bidirectional"))
    )
    (net (code "49") (name "unconnected-(SOC1-IO33-Pad9)") (class "Default")
      (node (ref "SOC1") (pin "9") (pinfunction "IO33_9") (pintype "bidirectional"))
    )
    (net (code "50") (name "unconnected-(SOC1-IO36-Pad4)") (class "Default")
      (node (ref "SOC1") (pin "4") (pinfunction "IO36_4") (pintype "bidirectional"))
    )
    (net (code "51") (name "unconnected-(SOC1-IO39-Pad5)") (class "Default")
      (node (ref "SOC1") (pin "5") (pinfunction "IO39_5") (pintype "bidirectional"))
    )
    (net (code "52") (name "unconnected-(U1-CTS-Pad23)") (class "Default")
      (node (ref "U1") (pin "23") (pinfunction "CTS_23") (pintype "passive"))
    )
    (net (code "53") (name "unconnected-(U1-DCD-Pad1)") (class "Default")
      (node (ref "U1") (pin "1") (pinfunction "DCD_1") (pintype "passive"))
    )
    (net (code "54") (name "unconnected-(U1-DSR-Pad27)") (class "Default")
      (node (ref "U1") (pin "27") (pinfunction "DSR_27") (pintype "passive"))
    )
    (net (code "55") (name "unconnected-(U1-RI-Pad2)") (class "Default")
      (node (ref "U1") (pin "2") (pinfunction "RI_2") (pintype "passive"))
    )
    (net (code "56") (name "unconnected-(U1-SUSPEND-Pad12)") (class "Default")
      (node (ref "U1") (pin "12") (pinfunction "SUSPEND_12") (pintype "passive"))
    )
    (net (code "57") (name "unconnected-(U1-~{RST}-Pad9)") (class "Default")
      (node (ref "U1") (pin "9") (pinfunction "~{RST}_9") (pintype "bidirectional"))
    )
    (net (code "58") (name "unconnected-(U1-~{SUSPEND}-Pad11)") (class "Default")
      (node (ref "U1") (pin "11") (pinfunction "~{SUSPEND}_11") (pintype "output"))
    )
    (net (code "59") (name "unconnected-(U4-32KHZ-Pad1)") (class "Default")
      (node (ref "U4") (pin "1") (pinfunction "32KHZ_1") (pintype "output"))
    )
    (net (code "60") (name "unconnected-(U4-~{INT}{slash}SQW-Pad3)") (class "Default")
      (node (ref "U4") (pin "3") (pinfunction "~{INT}/SQW_3") (pintype "output"))
    )
    (net (code "61") (name "unconnected-(U4-~{RST}-Pad4)") (class "Default")
      (node (ref "U4") (pin "4") (pinfunction "~{RST}_4") (pintype "passive"))
    )
  )
)
